# SCH_slime-vr_2022-07-10.net
KiCad netlist of a schematic drawn in EasyEDA
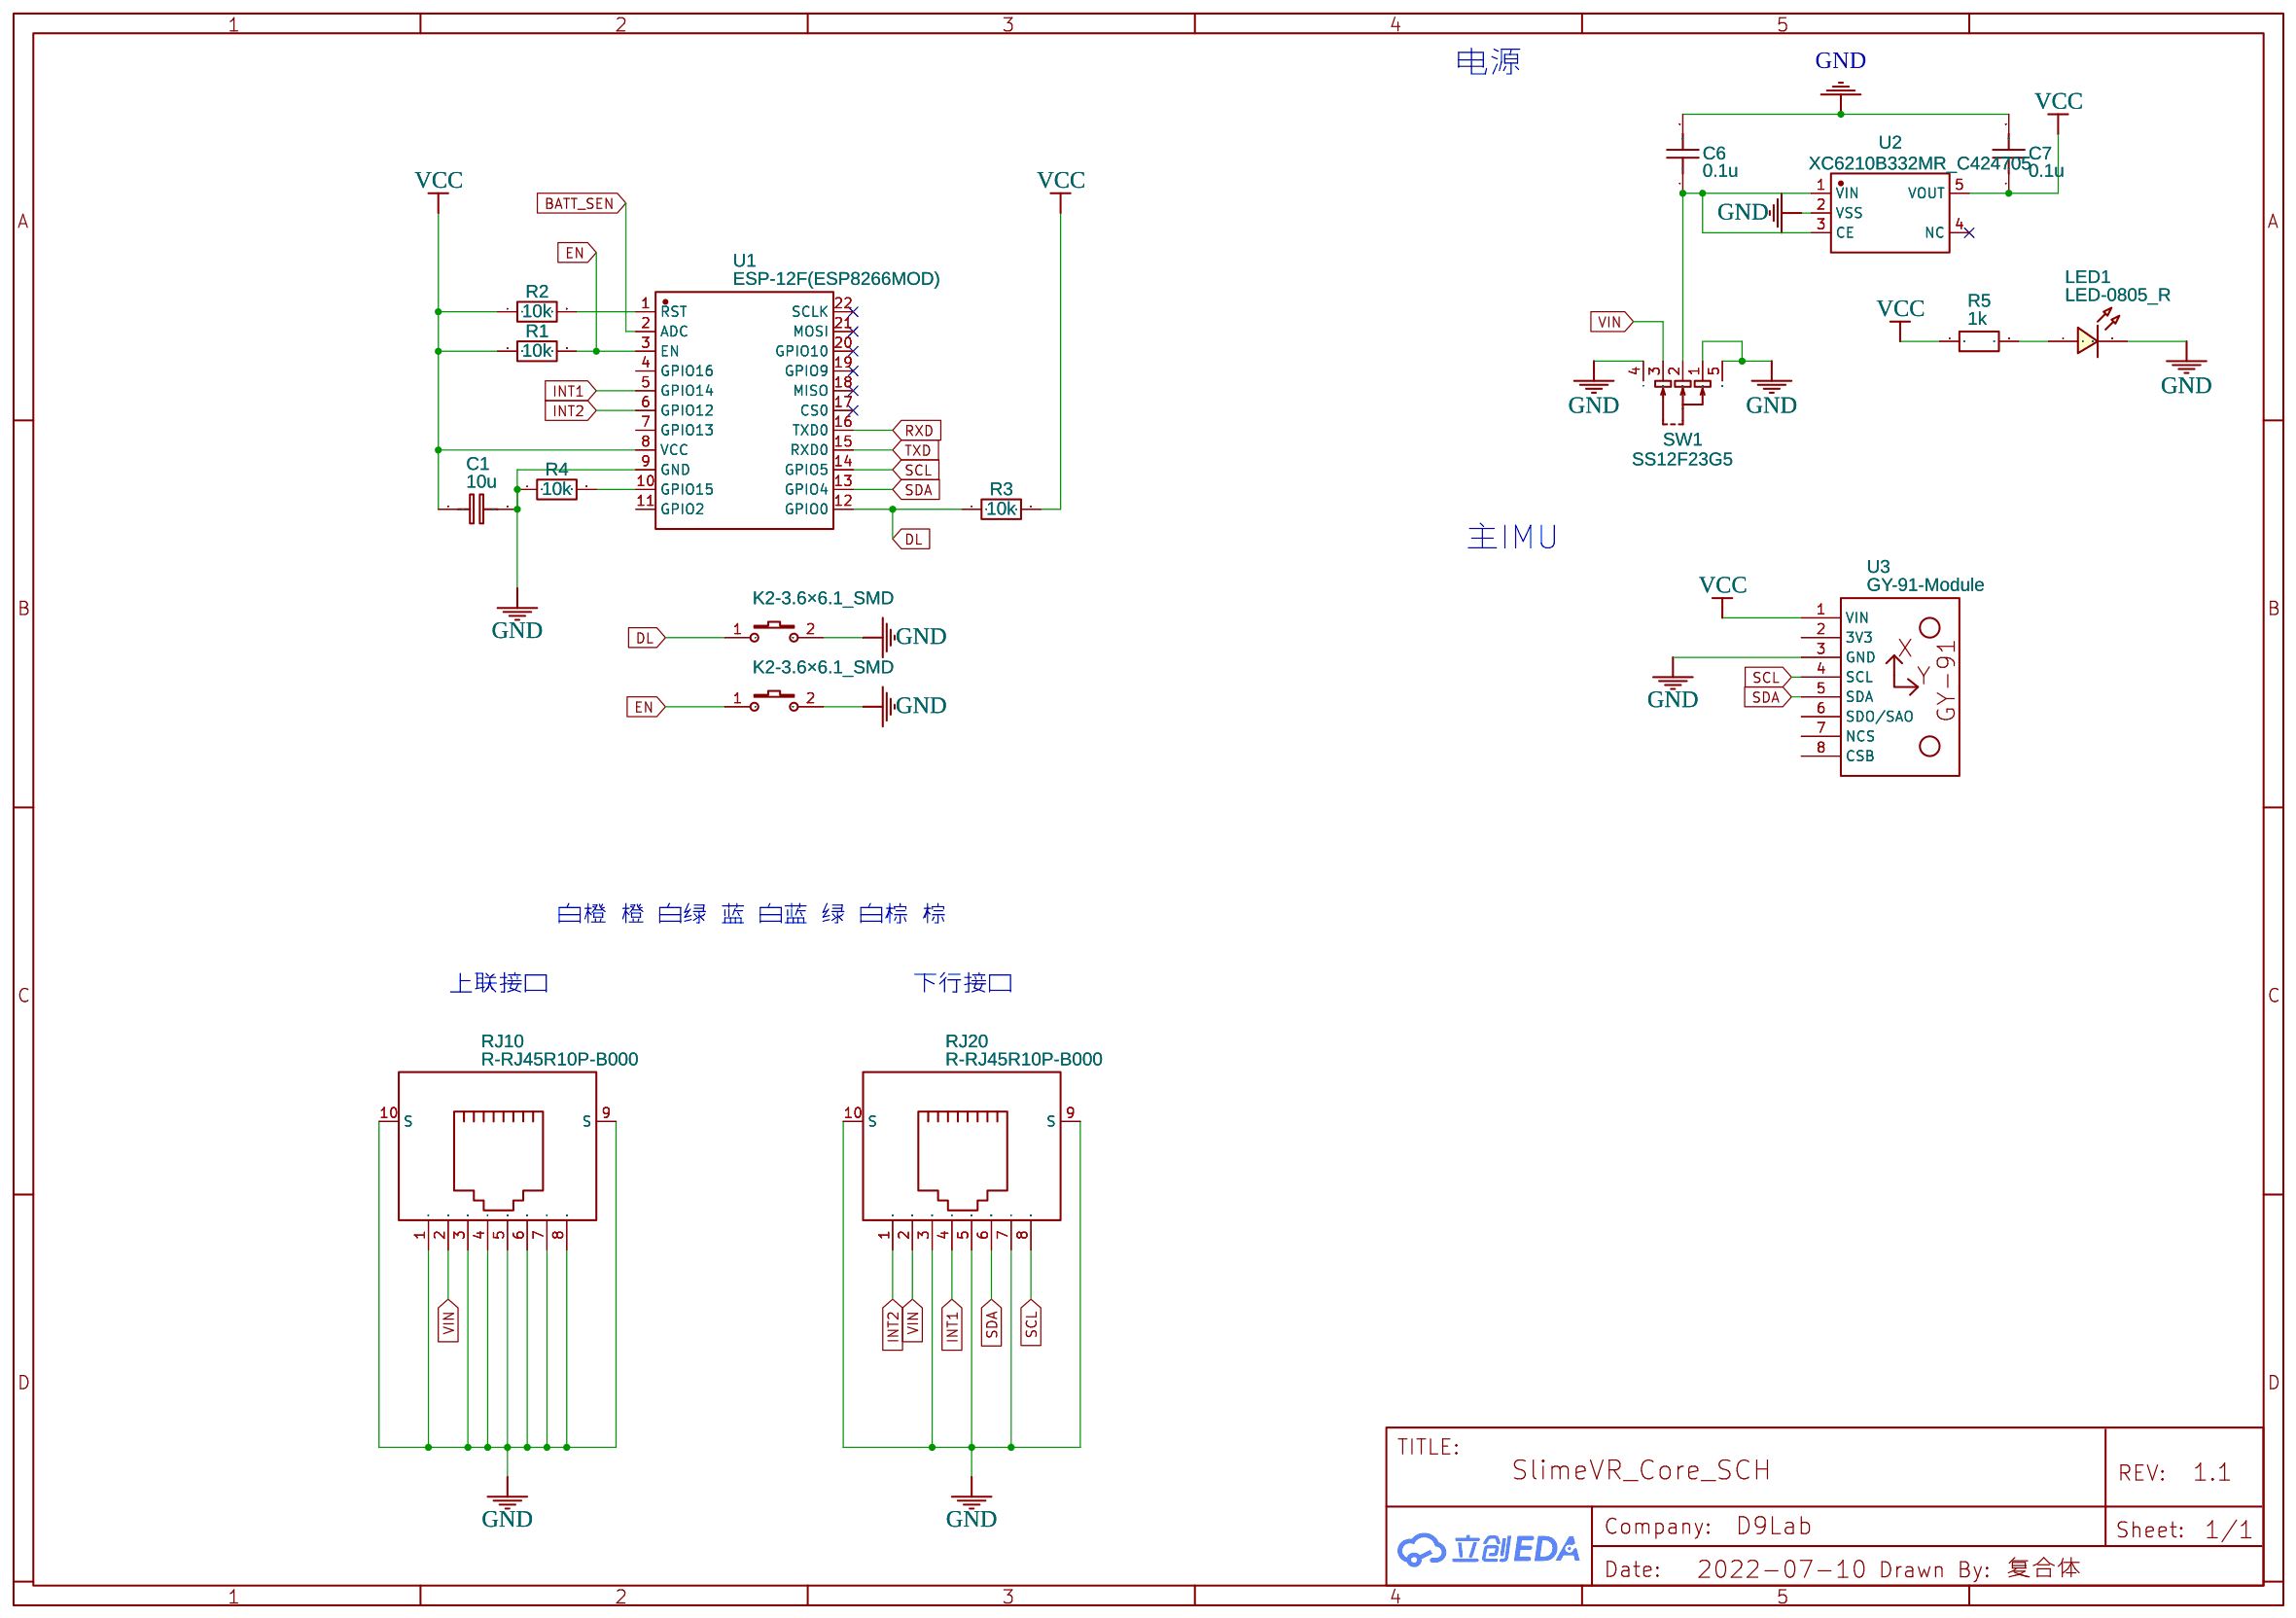
[diagram p0: SlimeVR_Core_SCH]
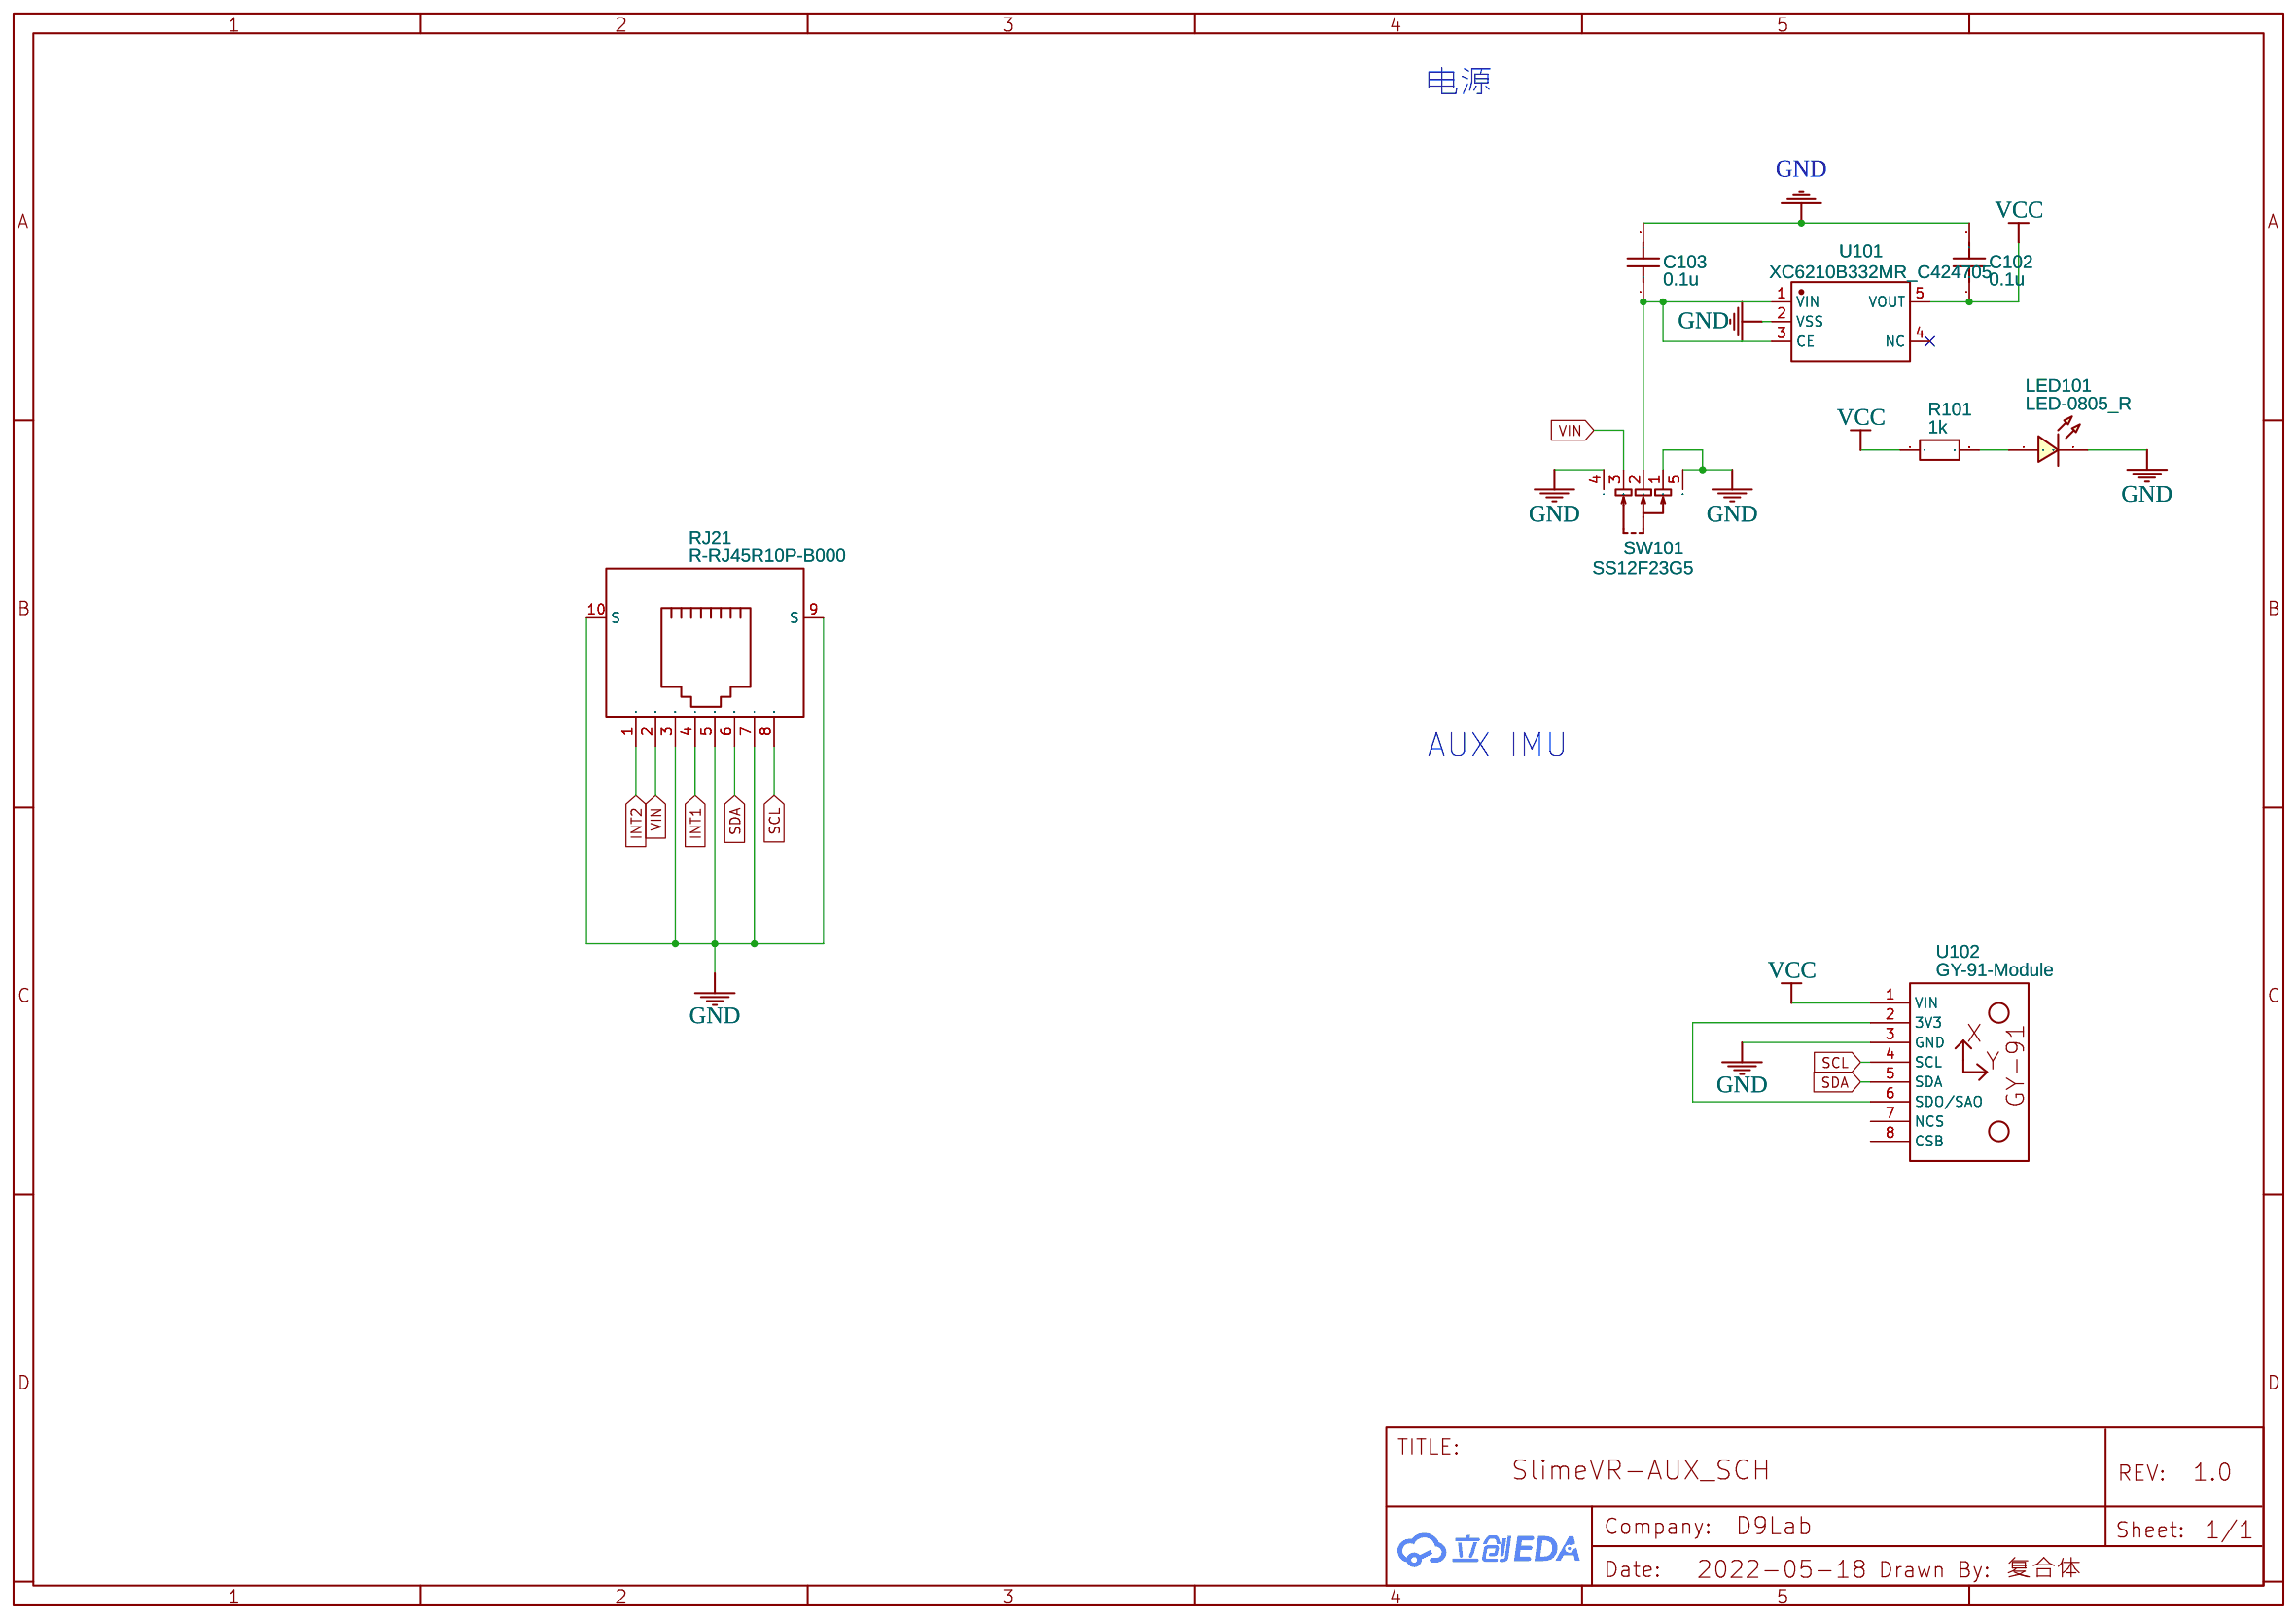
[diagram p1: SlimeVR-AUX_SCH]

(export (version "E")
  (design (tool "Eeschema 10.0.6"))
  (components
    (comp (ref "C1") (value "10u") (libsource (lib "") (part "C_0805_EU")))
    (comp (ref "C6") (value "0.1u") (libsource (lib "") (part "C_0805_US")))
    (comp (ref "C7") (value "0.1u") (libsource (lib "") (part "C_0805_US")))
    (comp (ref "DL")
      (value "K2-3.6×6.1_SMD")
      (fields
        (field (name "BOM_Manufacturer Part") "K2-1107ST-A4SW-06")
        (field (name "BOM_Supplier Part") "C118141")
      )
      (libsource (lib "") (part "K2-3.6×6.1_SMD_1"))
    )
    (comp (ref "EN")
      (value "K2-3.6×6.1_SMD")
      (fields
        (field (name "BOM_Manufacturer Part") "K2-1107ST-A4SW-06")
        (field (name "BOM_Supplier Part") "C118141")
      )
      (libsource (lib "") (part "K2-3.6×6.1_SMD"))
    )
    (comp (ref "LED1")
      (value "LED-0805_R")
      (fields
        (field (name "BOM_Manufacturer Part") "17-21SURC/S530-A3/TR8")
        (field (name "BOM_Supplier Part") "C72037")
      )
      (libsource (lib "") (part "LED-0805_R"))
    )
    (comp (ref "R1") (value "10k") (libsource (lib "") (part "R_0805_EU")))
    (comp (ref "R2") (value "10k") (libsource (lib "") (part "R_0805_EU")))
    (comp (ref "R3") (value "10k") (libsource (lib "") (part "R_0805_EU")))
    (comp (ref "R4") (value "10k") (libsource (lib "") (part "R_0805_EU")))
    (comp (ref "R5") (value "1k") (libsource (lib "") (part "R_0805_EU")))
    (comp (ref "RJ10")
      (value "R-RJ45R10P-B000")
      (fields (field (name "BOM_Supplier Part") "C386758"))
      (libsource (lib "") (part "R-RJ45R10P-B000"))
    )
    (comp (ref "RJ20")
      (value "R-RJ45R10P-B000")
      (fields (field (name "BOM_Supplier Part") "C386758"))
      (libsource (lib "") (part "R-RJ45R10P-B000"))
    )
    (comp (ref "SW1")
      (value "SS12F23G5")
      (fields (field (name "BOM_Supplier Part") "C2887262"))
      (libsource (lib "") (part "SS12F23G5"))
    )
    (comp (ref "U1")
      (value "ESP-12F(ESP8266MOD)")
      (fields (field (name "BOM_Supplier Part") "C82891"))
      (libsource (lib "") (part "ESP-12F(ESP8266MOD)"))
    )
    (comp (ref "U2")
      (value "XC6210B332MR_C424705")
      (fields
        (field (name "BOM_Manufacturer Part") "XC6210B332MR")
        (field (name "BOM_Supplier Part") "C424705")
      )
      (libsource (lib "") (part "XC6210B332MR_C424705"))
    )
    (comp (ref "U3")
      (value "GY-91-Module")
      (fields (field (name "BOM_Manufacturer Part") "GY-91 MPU9250 + BMP280"))
      (libsource (lib "") (part "GY-91-Module"))
    )
    (comp (ref "C102") (value "0.1u") (libsource (lib "") (part "C_0805_US")))
    (comp (ref "C103") (value "0.1u") (libsource (lib "") (part "C_0805_US")))
    (comp (ref "LED101")
      (value "LED-0805_R")
      (fields
        (field (name "BOM_Manufacturer Part") "17-21SURC/S530-A3/TR8")
        (field (name "BOM_Supplier Part") "C72037")
      )
      (libsource (lib "") (part "LED-0805_R"))
    )
    (comp (ref "R101") (value "1k") (libsource (lib "") (part "R_0805_EU")))
    (comp (ref "RJ21")
      (value "R-RJ45R10P-B000")
      (fields (field (name "BOM_Supplier Part") "C386758"))
      (libsource (lib "") (part "R-RJ45R10P-B000"))
    )
    (comp (ref "SW101")
      (value "SS12F23G5")
      (fields (field (name "BOM_Supplier Part") "C2887262"))
      (libsource (lib "") (part "SS12F23G5"))
    )
    (comp (ref "U101")
      (value "XC6210B332MR_C424705")
      (fields
        (field (name "BOM_Manufacturer Part") "XC6210B332MR")
        (field (name "BOM_Supplier Part") "C424705")
      )
      (libsource (lib "") (part "XC6210B332MR_C424705"))
    )
    (comp (ref "U102")
      (value "GY-91-Module")
      (fields (field (name "BOM_Manufacturer Part") "GY-91 MPU9250 + BMP280"))
      (libsource (lib "") (part "GY-91-Module"))
    )
  )
  (nets
    (net (code "1") (name "BATT_SEN") (class "Default")
      (node (ref "U1") (pin "2") (pinfunction "ADC_2") (pintype "unspecified"))
    )
    (net (code "2") (name "DL") (class "Default")
      (node (ref "DL") (pin "1") (pinfunction "1_1") (pintype "unspecified"))
      (node (ref "R3") (pin "1") (pinfunction "1_1") (pintype "unspecified"))
      (node (ref "U1") (pin "12") (pinfunction "GPIO0_12") (pintype "unspecified"))
    )
    (net (code "3") (name "EN") (class "Default")
      (node (ref "EN") (pin "1") (pinfunction "1_1") (pintype "unspecified"))
      (node (ref "R1") (pin "2") (pinfunction "2_2") (pintype "unspecified"))
      (node (ref "U1") (pin "3") (pinfunction "EN_3") (pintype "unspecified"))
    )
    (net (code "4") (name "GND") (class "Default")
      (node (ref "C1") (pin "2") (pinfunction "2_2") (pintype "unspecified"))
      (node (ref "C102") (pin "2") (pinfunction "2_2") (pintype "unspecified"))
      (node (ref "C103") (pin "2") (pinfunction "2_2") (pintype "unspecified"))
      (node (ref "C6") (pin "2") (pinfunction "2_2") (pintype "unspecified"))
      (node (ref "C7") (pin "2") (pinfunction "2_2") (pintype "unspecified"))
      (node (ref "DL") (pin "2") (pinfunction "2_2") (pintype "unspecified"))
      (node (ref "EN") (pin "2") (pinfunction "2_2") (pintype "unspecified"))
      (node (ref "LED1") (pin "2") (pinfunction "2_2") (pintype "unspecified"))
      (node (ref "LED101") (pin "2") (pinfunction "2_2") (pintype "unspecified"))
      (node (ref "R4") (pin "1") (pinfunction "1_1") (pintype "unspecified"))
      (node (ref "RJ10") (pin "1") (pinfunction "1_1") (pintype "unspecified"))
      (node (ref "RJ10") (pin "10") (pinfunction "S_10") (pintype "unspecified"))
      (node (ref "RJ10") (pin "3") (pinfunction "3_3") (pintype "unspecified"))
      (node (ref "RJ10") (pin "4") (pinfunction "4_4") (pintype "unspecified"))
      (node (ref "RJ10") (pin "5") (pinfunction "5_5") (pintype "unspecified"))
      (node (ref "RJ10") (pin "6") (pinfunction "6_6") (pintype "unspecified"))
      (node (ref "RJ10") (pin "7") (pinfunction "7_7") (pintype "unspecified"))
      (node (ref "RJ10") (pin "8") (pinfunction "8_8") (pintype "unspecified"))
      (node (ref "RJ10") (pin "9") (pinfunction "S_9") (pintype "unspecified"))
      (node (ref "RJ20") (pin "10") (pinfunction "S_10") (pintype "unspecified"))
      (node (ref "RJ20") (pin "3") (pinfunction "3_3") (pintype "unspecified"))
      (node (ref "RJ20") (pin "5") (pinfunction "5_5") (pintype "unspecified"))
      (node (ref "RJ20") (pin "7") (pinfunction "7_7") (pintype "unspecified"))
      (node (ref "RJ20") (pin "9") (pinfunction "S_9") (pintype "unspecified"))
      (node (ref "RJ21") (pin "10") (pinfunction "S_10") (pintype "unspecified"))
      (node (ref "RJ21") (pin "3") (pinfunction "3_3") (pintype "unspecified"))
      (node (ref "RJ21") (pin "5") (pinfunction "5_5") (pintype "unspecified"))
      (node (ref "RJ21") (pin "7") (pinfunction "7_7") (pintype "unspecified"))
      (node (ref "RJ21") (pin "9") (pinfunction "S_9") (pintype "unspecified"))
      (node (ref "SW1") (pin "1") (pinfunction "1_1") (pintype "unspecified"))
      (node (ref "SW1") (pin "4") (pinfunction "4_4") (pintype "unspecified"))
      (node (ref "SW1") (pin "5") (pinfunction "5_5") (pintype "unspecified"))
      (node (ref "SW101") (pin "1") (pinfunction "1_1") (pintype "unspecified"))
      (node (ref "SW101") (pin "4") (pinfunction "4_4") (pintype "unspecified"))
      (node (ref "SW101") (pin "5") (pinfunction "5_5") (pintype "unspecified"))
      (node (ref "U1") (pin "9") (pinfunction "GND_9") (pintype "unspecified"))
      (node (ref "U101") (pin "2") (pinfunction "VSS_2") (pintype "unspecified"))
      (node (ref "U102") (pin "3") (pinfunction "GND_3") (pintype "unspecified"))
      (node (ref "U2") (pin "2") (pinfunction "VSS_2") (pintype "unspecified"))
      (node (ref "U3") (pin "3") (pinfunction "GND_3") (pintype "unspecified"))
    )
    (net (code "5") (name "INT1") (class "Default")
      (node (ref "RJ20") (pin "4") (pinfunction "4_4") (pintype "unspecified"))
      (node (ref "RJ21") (pin "4") (pinfunction "4_4") (pintype "unspecified"))
      (node (ref "U1") (pin "5") (pinfunction "GPIO14_5") (pintype "unspecified"))
    )
    (net (code "6") (name "INT2") (class "Default")
      (node (ref "RJ20") (pin "1") (pinfunction "1_1") (pintype "unspecified"))
      (node (ref "RJ21") (pin "1") (pinfunction "1_1") (pintype "unspecified"))
      (node (ref "U1") (pin "6") (pinfunction "GPIO12_6") (pintype "unspecified"))
    )
    (net (code "7") (name "Net-(LED1-Pad1)") (class "Default")
      (node (ref "LED1") (pin "1") (pinfunction "1_1") (pintype "unspecified"))
      (node (ref "R5") (pin "2") (pinfunction "2_2") (pintype "unspecified"))
    )
    (net (code "8") (name "Net-(LED101-Pad1)") (class "Default")
      (node (ref "LED101") (pin "1") (pinfunction "1_1") (pintype "unspecified"))
      (node (ref "R101") (pin "2") (pinfunction "2_2") (pintype "unspecified"))
    )
    (net (code "9") (name "Net-(U1-GPIO15)") (class "Default")
      (node (ref "R4") (pin "2") (pinfunction "2_2") (pintype "unspecified"))
      (node (ref "U1") (pin "10") (pinfunction "GPIO15_10") (pintype "unspecified"))
    )
    (net (code "10") (name "Net-(U1-RST)") (class "Default")
      (node (ref "R2") (pin "2") (pinfunction "2_2") (pintype "unspecified"))
      (node (ref "U1") (pin "1") (pinfunction "RST_1") (pintype "unspecified"))
    )
    (net (code "11") (name "Net-(U2-CE)") (class "Default")
      (node (ref "C6") (pin "1") (pinfunction "1_1") (pintype "unspecified"))
      (node (ref "SW1") (pin "2") (pinfunction "2_2") (pintype "unspecified"))
      (node (ref "U2") (pin "1") (pinfunction "VIN_1") (pintype "unspecified"))
      (node (ref "U2") (pin "3") (pinfunction "CE_3") (pintype "unspecified"))
    )
    (net (code "12") (name "Net-(U101-CE)") (class "Default")
      (node (ref "C103") (pin "1") (pinfunction "1_1") (pintype "unspecified"))
      (node (ref "SW101") (pin "2") (pinfunction "2_2") (pintype "unspecified"))
      (node (ref "U101") (pin "1") (pinfunction "VIN_1") (pintype "unspecified"))
      (node (ref "U101") (pin "3") (pinfunction "CE_3") (pintype "unspecified"))
    )
    (net (code "13") (name "Net-(U102-3V3)") (class "Default")
      (node (ref "U102") (pin "2") (pinfunction "3V3_2") (pintype "unspecified"))
      (node (ref "U102") (pin "6") (pinfunction "SDO/SAO_6") (pintype "unspecified"))
    )
    (net (code "14") (name "RXD") (class "Default")
      (node (ref "U1") (pin "16") (pinfunction "TXD0_16") (pintype "unspecified"))
    )
    (net (code "15") (name "SCL") (class "Default")
      (node (ref "RJ20") (pin "8") (pinfunction "8_8") (pintype "unspecified"))
      (node (ref "RJ21") (pin "8") (pinfunction "8_8") (pintype "unspecified"))
      (node (ref "U1") (pin "14") (pinfunction "GPIO5_14") (pintype "unspecified"))
      (node (ref "U102") (pin "4") (pinfunction "SCL_4") (pintype "unspecified"))
      (node (ref "U3") (pin "4") (pinfunction "SCL_4") (pintype "unspecified"))
    )
    (net (code "16") (name "SDA") (class "Default")
      (node (ref "RJ20") (pin "6") (pinfunction "6_6") (pintype "unspecified"))
      (node (ref "RJ21") (pin "6") (pinfunction "6_6") (pintype "unspecified"))
      (node (ref "U1") (pin "13") (pinfunction "GPIO4_13") (pintype "unspecified"))
      (node (ref "U102") (pin "5") (pinfunction "SDA_5") (pintype "unspecified"))
      (node (ref "U3") (pin "5") (pinfunction "SDA_5") (pintype "unspecified"))
    )
    (net (code "17") (name "TXD") (class "Default")
      (node (ref "U1") (pin "15") (pinfunction "RXD0_15") (pintype "unspecified"))
    )
    (net (code "18") (name "VCC") (class "Default")
      (node (ref "C1") (pin "1") (pinfunction "1_1") (pintype "unspecified"))
      (node (ref "C102") (pin "1") (pinfunction "1_1") (pintype "unspecified"))
      (node (ref "C7") (pin "1") (pinfunction "1_1") (pintype "unspecified"))
      (node (ref "R1") (pin "1") (pinfunction "1_1") (pintype "unspecified"))
      (node (ref "R101") (pin "1") (pinfunction "1_1") (pintype "unspecified"))
      (node (ref "R2") (pin "1") (pinfunction "1_1") (pintype "unspecified"))
      (node (ref "R3") (pin "2") (pinfunction "2_2") (pintype "unspecified"))
      (node (ref "R5") (pin "1") (pinfunction "1_1") (pintype "unspecified"))
      (node (ref "U1") (pin "8") (pinfunction "VCC_8") (pintype "unspecified"))
      (node (ref "U101") (pin "5") (pinfunction "VOUT_5") (pintype "unspecified"))
      (node (ref "U102") (pin "1") (pinfunction "VIN_1") (pintype "unspecified"))
      (node (ref "U2") (pin "5") (pinfunction "VOUT_5") (pintype "unspecified"))
      (node (ref "U3") (pin "1") (pinfunction "VIN_1") (pintype "unspecified"))
    )
    (net (code "19") (name "VIN") (class "Default")
      (node (ref "RJ10") (pin "2") (pinfunction "2_2") (pintype "unspecified"))
      (node (ref "RJ20") (pin "2") (pinfunction "2_2") (pintype "unspecified"))
      (node (ref "RJ21") (pin "2") (pinfunction "2_2") (pintype "unspecified"))
      (node (ref "SW1") (pin "3") (pinfunction "3_3") (pintype "unspecified"))
      (node (ref "SW101") (pin "3") (pinfunction "3_3") (pintype "unspecified"))
    )
    (net (code "20") (name "unconnected-(U1-CS0-Pad17)") (class "Default")
      (node (ref "U1") (pin "17") (pinfunction "CS0_17") (pintype "unspecified+no_connect"))
    )
    (net (code "21") (name "unconnected-(U1-GPIO2-Pad11)") (class "Default")
      (node (ref "U1") (pin "11") (pinfunction "GPIO2_11") (pintype "unspecified"))
    )
    (net (code "22") (name "unconnected-(U1-GPIO9-Pad19)") (class "Default")
      (node (ref "U1") (pin "19") (pinfunction "GPIO9_19") (pintype "unspecified+no_connect"))
    )
    (net (code "23") (name "unconnected-(U1-GPIO10-Pad20)") (class "Default")
      (node (ref "U1") (pin "20") (pinfunction "GPIO10_20") (pintype "unspecified+no_connect"))
    )
    (net (code "24") (name "unconnected-(U1-GPIO13-Pad7)") (class "Default")
      (node (ref "U1") (pin "7") (pinfunction "GPIO13_7") (pintype "unspecified"))
    )
    (net (code "25") (name "unconnected-(U1-GPIO16-Pad4)") (class "Default")
      (node (ref "U1") (pin "4") (pinfunction "GPIO16_4") (pintype "unspecified"))
    )
    (net (code "26") (name "unconnected-(U1-MISO-Pad18)") (class "Default")
      (node (ref "U1") (pin "18") (pinfunction "MISO_18") (pintype "unspecified+no_connect"))
    )
    (net (code "27") (name "unconnected-(U1-MOSI-Pad21)") (class "Default")
      (node (ref "U1") (pin "21") (pinfunction "MOSI_21") (pintype "unspecified+no_connect"))
    )
    (net (code "28") (name "unconnected-(U1-SCLK-Pad22)") (class "Default")
      (node (ref "U1") (pin "22") (pinfunction "SCLK_22") (pintype "unspecified+no_connect"))
    )
    (net (code "29") (name "unconnected-(U2-NC-Pad4)") (class "Default")
      (node (ref "U2") (pin "4") (pinfunction "NC_4") (pintype "unspecified+no_connect"))
    )
    (net (code "30") (name "unconnected-(U3-3V3-Pad2)") (class "Default")
      (node (ref "U3") (pin "2") (pinfunction "3V3_2") (pintype "unspecified"))
    )
    (net (code "31") (name "unconnected-(U3-CSB-Pad8)") (class "Default")
      (node (ref "U3") (pin "8") (pinfunction "CSB_8") (pintype "unspecified"))
    )
    (net (code "32") (name "unconnected-(U3-NCS-Pad7)") (class "Default")
      (node (ref "U3") (pin "7") (pinfunction "NCS_7") (pintype "unspecified"))
    )
    (net (code "33") (name "unconnected-(U3-SDO{slash}SAO-Pad6)") (class "Default")
      (node (ref "U3") (pin "6") (pinfunction "SDO/SAO_6") (pintype "unspecified"))
    )
    (net (code "34") (name "unconnected-(U101-NC-Pad4)") (class "Default")
      (node (ref "U101") (pin "4") (pinfunction "NC_4") (pintype "unspecified+no_connect"))
    )
    (net (code "35") (name "unconnected-(U102-CSB-Pad8)") (class "Default")
      (node (ref "U102") (pin "8") (pinfunction "CSB_8") (pintype "unspecified"))
    )
    (net (code "36") (name "unconnected-(U102-NCS-Pad7)") (class "Default")
      (node (ref "U102") (pin "7") (pinfunction "NCS_7") (pintype "unspecified"))
    )
  )
)
